# mini_Quad_v01_1_L.net
KiCad netlist of a schematic drawn in EAGLE
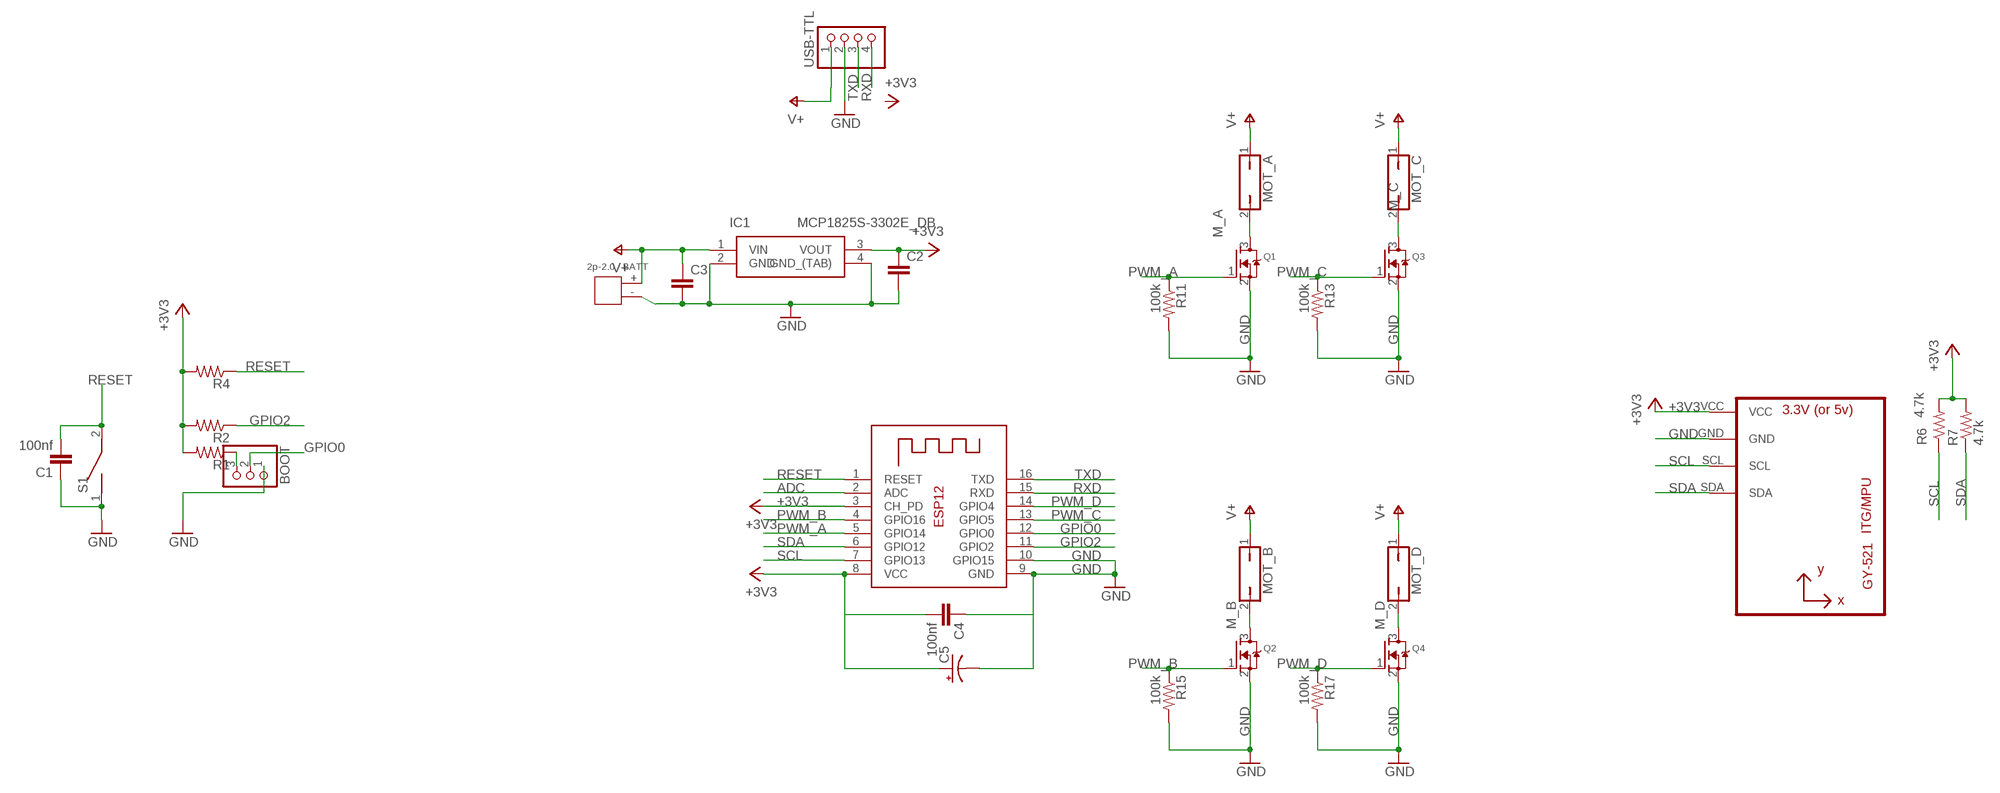
[diagram p0: schematic, sheet 1]

(export (version "E")
  (design (tool "Eeschema 10.0.6"))
  (components
    (comp (ref "BATT")
      (value "2p-2.0")
      (footprint "eagle-import:H2-2.0-6X4.5MM")
      (libsource (lib "eagle-import") (part "DIP-JST-2P-2.0"))
    )
    (comp (ref "BOOT")
      (value "PINHD-1X3")
      (footprint "eagle-import:1X03")
      (libsource (lib "eagle-import") (part "PINHD-1X3"))
    )
    (comp (ref "C1")
      (value "100nf")
      (footprint "eagle-import:C1206K")
      (libsource (lib "eagle-import") (part "C-EUC1206K"))
    )
    (comp (ref "C2")
      (value "C-EUC1206K")
      (footprint "eagle-import:C1206K")
      (libsource (lib "eagle-import") (part "C-EUC1206K"))
    )
    (comp (ref "C3")
      (value "C-EUC1206K")
      (footprint "eagle-import:C1206K")
      (libsource (lib "eagle-import") (part "C-EUC1206K"))
    )
    (comp (ref "C4")
      (value "100nf")
      (footprint "eagle-import:C050-024X044")
      (libsource (lib "eagle-import") (part "C-EU050-024X044"))
    )
    (comp (ref "C5")
      (value "CPOL-USB/3528-21W")
      (footprint "eagle-import:B_3528-21W")
      (libsource (lib "eagle-import") (part "CPOL-USB/3528-21W"))
    )
    (comp (ref "ESP12-E")
      (value "ESP-12")
      (footprint "eagle-import:ESP-12")
      (libsource (lib "eagle-import") (part "ESP-12"))
    )
    (comp (ref "IC1")
      (value "MCP1825S-3302E_DB")
      (footprint "eagle-import:SOT230P700X180-4N")
      (fields
        (field (name "ARROW_PART_NUMBER") "MCP1825S-3302E/DB")
        (field (name "RS_PART_NUMBER") "9115520")
      )
      (libsource (lib "eagle-import") (part "MCP1825S-3302E_DB"))
    )
    (comp (ref "MOT_A")
      (value "JP1Q")
      (footprint "eagle-import:JP1")
      (libsource (lib "eagle-import") (part "JP1Q"))
    )
    (comp (ref "MOT_B")
      (value "JP1Q")
      (footprint "eagle-import:JP1")
      (libsource (lib "eagle-import") (part "JP1Q"))
    )
    (comp (ref "MOT_C")
      (value "JP1Q")
      (footprint "eagle-import:JP1")
      (libsource (lib "eagle-import") (part "JP1Q"))
    )
    (comp (ref "MOT_D")
      (value "JP1Q")
      (footprint "eagle-import:JP1")
      (libsource (lib "eagle-import") (part "JP1Q"))
    )
    (comp (ref "Q1")
      (value "MOSFET-NTO252")
      (footprint "eagle-import:TO252")
      (libsource (lib "eagle-import") (part "MOSFET-NTO252"))
    )
    (comp (ref "Q2")
      (value "MOSFET-NTO252")
      (footprint "eagle-import:TO252")
      (libsource (lib "eagle-import") (part "MOSFET-NTO252"))
    )
    (comp (ref "Q3")
      (value "MOSFET-NTO252")
      (footprint "eagle-import:TO252")
      (libsource (lib "eagle-import") (part "MOSFET-NTO252"))
    )
    (comp (ref "Q4")
      (value "MOSFET-NTO252")
      (footprint "eagle-import:TO252")
      (libsource (lib "eagle-import") (part "MOSFET-NTO252"))
    )
    (comp (ref "R1")
      (value "R-US_R1206W")
      (footprint "eagle-import:R1206W")
      (libsource (lib "eagle-import") (part "R-US_R1206W"))
    )
    (comp (ref "R2")
      (value "R-US_0204/5")
      (footprint "eagle-import:0204_5")
      (libsource (lib "eagle-import") (part "R-US_0204/5"))
    )
    (comp (ref "R4")
      (value "R-US_0204/7")
      (footprint "eagle-import:0204_7")
      (libsource (lib "eagle-import") (part "R-US_0204/7"))
    )
    (comp (ref "R6")
      (value "4.7k")
      (footprint "eagle-import:0204_5")
      (libsource (lib "eagle-import") (part "R-US_0204/5"))
    )
    (comp (ref "R7")
      (value "4.7k")
      (footprint "eagle-import:0204_7")
      (libsource (lib "eagle-import") (part "R-US_0204/7"))
    )
    (comp (ref "R11")
      (value "100k")
      (footprint "eagle-import:0204_5")
      (libsource (lib "eagle-import") (part "R-US_0204/5"))
    )
    (comp (ref "R13")
      (value "100k")
      (footprint "eagle-import:0204_5")
      (libsource (lib "eagle-import") (part "R-US_0204/5"))
    )
    (comp (ref "R15")
      (value "100k")
      (footprint "eagle-import:0204_5")
      (libsource (lib "eagle-import") (part "R-US_0204/5"))
    )
    (comp (ref "R17")
      (value "100k")
      (footprint "eagle-import:0204_5")
      (libsource (lib "eagle-import") (part "R-US_0204/5"))
    )
    (comp (ref "S1")
      (value "DS01")
      (footprint "eagle-import:DS-01")
      (libsource (lib "eagle-import") (part "DS01"))
    )
    (comp (ref "U1")
      (value "GY-521MPU6050")
      (footprint "eagle-import:GY-521")
      (libsource (lib "eagle-import") (part "GY-521MPU6050"))
    )
    (comp (ref "USB-TTL")
      (value "PINHD-1X4")
      (footprint "eagle-import:1X04")
      (libsource (lib "eagle-import") (part "PINHD-1X4"))
    )
  )
  (nets
    (net (code "1") (name "+3V3") (class "Default")
      (node (ref "C2") (pin "1") (pinfunction "1_1") (pintype "passive"))
      (node (ref "C4") (pin "2") (pinfunction "2_2") (pintype "passive"))
      (node (ref "C5") (pin "+") (pinfunction "+_+") (pintype "passive"))
      (node (ref "ESP12-E") (pin "3") (pinfunction "CH_PD_3") (pintype "input"))
      (node (ref "ESP12-E") (pin "8") (pinfunction "VCC_8") (pintype "power_in"))
      (node (ref "IC1") (pin "3") (pinfunction "VOUT_3") (pintype "output"))
      (node (ref "R1") (pin "2") (pinfunction "2_2") (pintype "passive"))
      (node (ref "R2") (pin "2") (pinfunction "2_2") (pintype "passive"))
      (node (ref "R4") (pin "2") (pinfunction "2_2") (pintype "passive"))
      (node (ref "R6") (pin "2") (pinfunction "2_2") (pintype "passive"))
      (node (ref "R7") (pin "2") (pinfunction "2_2") (pintype "passive"))
      (node (ref "U1") (pin "VCC") (pinfunction "VCC_VCC") (pintype "bidirectional"))
    )
    (net (code "2") (name "/ADC") (class "Default")
      (node (ref "ESP12-E") (pin "2") (pinfunction "ADC_2") (pintype "passive"))
    )
    (net (code "3") (name "/GPIO0") (class "Default")
      (node (ref "BOOT") (pin "2") (pinfunction "2_2") (pintype "passive"))
      (node (ref "ESP12-E") (pin "12") (pinfunction "GPIO0_12") (pintype "bidirectional"))
    )
    (net (code "4") (name "/GPIO2") (class "Default")
      (node (ref "ESP12-E") (pin "11") (pinfunction "GPIO2_11") (pintype "bidirectional"))
      (node (ref "R2") (pin "1") (pinfunction "1_1") (pintype "passive"))
    )
    (net (code "5") (name "/M_A") (class "Default")
      (node (ref "MOT_A") (pin "2") (pinfunction "2_2") (pintype "passive"))
      (node (ref "Q1") (pin "3") (pinfunction "D_3") (pintype "bidirectional"))
    )
    (net (code "6") (name "/M_B") (class "Default")
      (node (ref "MOT_B") (pin "2") (pinfunction "2_2") (pintype "passive"))
      (node (ref "Q2") (pin "3") (pinfunction "D_3") (pintype "bidirectional"))
    )
    (net (code "7") (name "/M_C") (class "Default")
      (node (ref "MOT_C") (pin "2") (pinfunction "2_2") (pintype "passive"))
      (node (ref "Q3") (pin "3") (pinfunction "D_3") (pintype "bidirectional"))
    )
    (net (code "8") (name "/M_D") (class "Default")
      (node (ref "MOT_D") (pin "2") (pinfunction "2_2") (pintype "passive"))
      (node (ref "Q4") (pin "3") (pinfunction "D_3") (pintype "bidirectional"))
    )
    (net (code "9") (name "/PWM_A") (class "Default")
      (node (ref "ESP12-E") (pin "5") (pinfunction "GPIO14_5") (pintype "bidirectional"))
      (node (ref "Q1") (pin "1") (pinfunction "G_1") (pintype "bidirectional"))
      (node (ref "R11") (pin "1") (pinfunction "1_1") (pintype "passive"))
    )
    (net (code "10") (name "/PWM_B") (class "Default")
      (node (ref "ESP12-E") (pin "4") (pinfunction "GPIO16_4") (pintype "bidirectional"))
      (node (ref "Q2") (pin "1") (pinfunction "G_1") (pintype "bidirectional"))
      (node (ref "R15") (pin "1") (pinfunction "1_1") (pintype "passive"))
    )
    (net (code "11") (name "/PWM_C") (class "Default")
      (node (ref "ESP12-E") (pin "13") (pinfunction "GPIO5_13") (pintype "bidirectional"))
      (node (ref "Q3") (pin "1") (pinfunction "G_1") (pintype "bidirectional"))
      (node (ref "R13") (pin "1") (pinfunction "1_1") (pintype "passive"))
    )
    (net (code "12") (name "/PWM_D") (class "Default")
      (node (ref "ESP12-E") (pin "14") (pinfunction "GPIO4_14") (pintype "bidirectional"))
      (node (ref "Q4") (pin "1") (pinfunction "G_1") (pintype "bidirectional"))
      (node (ref "R17") (pin "1") (pinfunction "1_1") (pintype "passive"))
    )
    (net (code "13") (name "/RESET") (class "Default")
      (node (ref "C1") (pin "2") (pinfunction "2_2") (pintype "passive"))
      (node (ref "ESP12-E") (pin "1") (pinfunction "RESET_1") (pintype "input"))
      (node (ref "R4") (pin "1") (pinfunction "1_1") (pintype "passive"))
      (node (ref "S1") (pin "2") (pinfunction "2_2") (pintype "passive"))
    )
    (net (code "14") (name "/RXD") (class "Default")
      (node (ref "ESP12-E") (pin "15") (pinfunction "RXD_15") (pintype "input"))
      (node (ref "USB-TTL") (pin "4") (pinfunction "4_4") (pintype "passive"))
    )
    (net (code "15") (name "/SCL") (class "Default")
      (node (ref "ESP12-E") (pin "7") (pinfunction "GPIO13_7") (pintype "bidirectional"))
      (node (ref "R6") (pin "1") (pinfunction "1_1") (pintype "passive"))
      (node (ref "U1") (pin "SCL") (pinfunction "SCL_SCL") (pintype "bidirectional"))
    )
    (net (code "16") (name "/SDA") (class "Default")
      (node (ref "ESP12-E") (pin "6") (pinfunction "GPIO12_6") (pintype "bidirectional"))
      (node (ref "R7") (pin "1") (pinfunction "1_1") (pintype "passive"))
      (node (ref "U1") (pin "SDA") (pinfunction "SDA_SDA") (pintype "bidirectional"))
    )
    (net (code "17") (name "/TXD") (class "Default")
      (node (ref "ESP12-E") (pin "16") (pinfunction "TXD_16") (pintype "output"))
      (node (ref "USB-TTL") (pin "3") (pinfunction "3_3") (pintype "passive"))
    )
    (net (code "18") (name "GND") (class "Default")
      (node (ref "BATT") (pin "-") (pinfunction "P$2_-") (pintype "bidirectional"))
      (node (ref "BOOT") (pin "1") (pinfunction "1_1") (pintype "passive"))
      (node (ref "C1") (pin "1") (pinfunction "1_1") (pintype "passive"))
      (node (ref "C2") (pin "2") (pinfunction "2_2") (pintype "passive"))
      (node (ref "C3") (pin "2") (pinfunction "2_2") (pintype "passive"))
      (node (ref "C4") (pin "1") (pinfunction "1_1") (pintype "passive"))
      (node (ref "C5") (pin "-") (pinfunction "-_-") (pintype "passive"))
      (node (ref "ESP12-E") (pin "10") (pinfunction "GPIO15_10") (pintype "bidirectional"))
      (node (ref "ESP12-E") (pin "9") (pinfunction "GND_9") (pintype "power_in"))
      (node (ref "IC1") (pin "2") (pinfunction "GND_2") (pintype "power_in"))
      (node (ref "IC1") (pin "4") (pinfunction "GND_(TAB)_4") (pintype "power_in"))
      (node (ref "Q1") (pin "2") (pinfunction "S_2") (pintype "bidirectional"))
      (node (ref "Q2") (pin "2") (pinfunction "S_2") (pintype "bidirectional"))
      (node (ref "Q3") (pin "2") (pinfunction "S_2") (pintype "bidirectional"))
      (node (ref "Q4") (pin "2") (pinfunction "S_2") (pintype "bidirectional"))
      (node (ref "R11") (pin "2") (pinfunction "2_2") (pintype "passive"))
      (node (ref "R13") (pin "2") (pinfunction "2_2") (pintype "passive"))
      (node (ref "R15") (pin "2") (pinfunction "2_2") (pintype "passive"))
      (node (ref "R17") (pin "2") (pinfunction "2_2") (pintype "passive"))
      (node (ref "S1") (pin "1") (pinfunction "1_1") (pintype "passive"))
      (node (ref "U1") (pin "GND") (pinfunction "GND_GND") (pintype "bidirectional"))
      (node (ref "USB-TTL") (pin "2") (pinfunction "2_2") (pintype "passive"))
    )
    (net (code "19") (name "Net-(BOOT-Pad3)") (class "Default")
      (node (ref "BOOT") (pin "3") (pinfunction "3_3") (pintype "passive"))
      (node (ref "R1") (pin "1") (pinfunction "1_1") (pintype "passive"))
    )
    (net (code "20") (name "V+") (class "Default")
      (node (ref "BATT") (pin "+") (pinfunction "P$1_+") (pintype "bidirectional"))
      (node (ref "C3") (pin "1") (pinfunction "1_1") (pintype "passive"))
      (node (ref "IC1") (pin "1") (pinfunction "VIN_1") (pintype "input"))
      (node (ref "MOT_A") (pin "1") (pinfunction "1_1") (pintype "passive"))
      (node (ref "MOT_B") (pin "1") (pinfunction "1_1") (pintype "passive"))
      (node (ref "MOT_C") (pin "1") (pinfunction "1_1") (pintype "passive"))
      (node (ref "MOT_D") (pin "1") (pinfunction "1_1") (pintype "passive"))
      (node (ref "USB-TTL") (pin "1") (pinfunction "1_1") (pintype "passive"))
    )
  )
)
